# MB_Relay_active_high.net
KiCad netlist of a schematic drawn in EAGLE
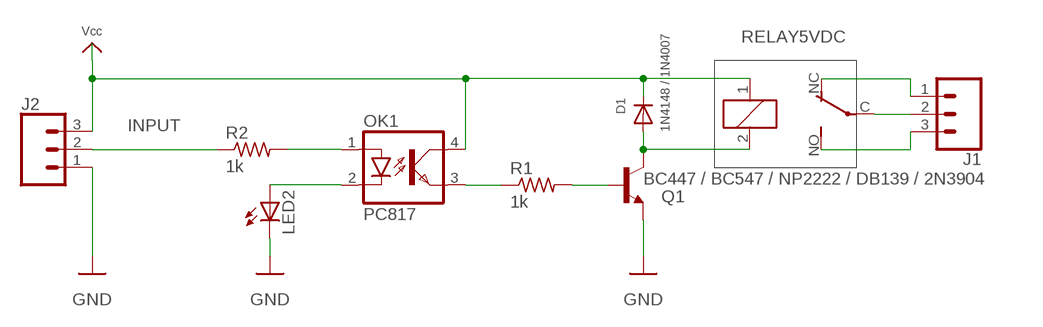
[diagram p0: schematic, sheet 1]

(export (version "E")
  (design (tool "Eeschema 10.0.6"))
  (components
    (comp (ref "D1")
      (value "1N4148 / 1N4007")
      (footprint "eagle-import:DO-1N4148")
      (libsource (lib "eagle-import") (part "DIODEDO-1N4148"))
    )
    (comp (ref "J1")
      (value "CONN_03")
      (footprint "eagle-import:1X03")
      (libsource (lib "eagle-import") (part "CONN_03"))
    )
    (comp (ref "J2")
      (value "CONN_03")
      (footprint "eagle-import:1X03")
      (libsource (lib "eagle-import") (part "CONN_03"))
    )
    (comp (ref "LED2")
      (value "LED3MM")
      (footprint "eagle-import:LED3MM")
      (libsource (lib "eagle-import") (part "LED3MM"))
    )
    (comp (ref "OK1")
      (value "PC817")
      (footprint "eagle-import:DIL04")
      (fields (field (name "MPN") "PC817X4J000F"))
      (libsource (lib "eagle-import") (part "PC817"))
    )
    (comp (ref "Q1")
      (value "BC447 / BC547 / NP2222 / DB139 / 2N3904")
      (footprint "eagle-import:TO92-EBC")
      (libsource (lib "eagle-import") (part "BC447"))
    )
    (comp (ref "R1")
      (value "1k")
      (footprint "eagle-import:0204_7")
      (libsource (lib "eagle-import") (part "R-US_0204/7"))
    )
    (comp (ref "R2")
      (value "1k")
      (footprint "eagle-import:0204_7")
      (libsource (lib "eagle-import") (part "R-US_0204/7"))
    )
    (comp (ref "RELAY5VDC")
      (value "RELAY 5VDC")
      (footprint "eagle-import:CQ1")
      (libsource (lib "eagle-import") (part "CQ1-12V"))
    )
  )
  (nets
    (net (code "1") (name "/INPUT") (class "Default")
      (node (ref "J2") (pin "2") (pinfunction "2_2") (pintype "passive"))
      (node (ref "R2") (pin "1") (pinfunction "1_1") (pintype "passive"))
    )
    (net (code "2") (name "GND") (class "Default")
      (node (ref "J2") (pin "1") (pinfunction "1_1") (pintype "passive"))
      (node (ref "LED2") (pin "K") (pinfunction "C_K") (pintype "passive"))
      (node (ref "Q1") (pin "E") (pinfunction "E_E") (pintype "passive"))
    )
    (net (code "3") (name "Net-(D1-PadA)") (class "Default")
      (node (ref "D1") (pin "A") (pinfunction "A_A") (pintype "passive"))
      (node (ref "Q1") (pin "C") (pinfunction "C_C") (pintype "passive"))
      (node (ref "RELAY5VDC") (pin "2") (pinfunction "2_2") (pintype "passive"))
    )
    (net (code "4") (name "Net-(OK1-A)") (class "Default")
      (node (ref "OK1") (pin "1") (pinfunction "A_1") (pintype "passive"))
      (node (ref "R2") (pin "2") (pinfunction "2_2") (pintype "passive"))
    )
    (net (code "5") (name "Net-(OK1-C)") (class "Default")
      (node (ref "LED2") (pin "A") (pinfunction "A_A") (pintype "passive"))
      (node (ref "OK1") (pin "2") (pinfunction "C_2") (pintype "passive"))
    )
    (net (code "6") (name "Net-(OK1-EMIT)") (class "Default")
      (node (ref "OK1") (pin "3") (pinfunction "EMIT_3") (pintype "passive"))
      (node (ref "R1") (pin "1") (pinfunction "1_1") (pintype "passive"))
    )
    (net (code "7") (name "Net-(Q1-PadB)") (class "Default")
      (node (ref "Q1") (pin "B") (pinfunction "B_B") (pintype "passive"))
      (node (ref "R1") (pin "2") (pinfunction "2_2") (pintype "passive"))
    )
    (net (code "8") (name "Net-(RELAY5VDCB-O)") (class "Default")
      (node (ref "J1") (pin "1") (pinfunction "1_1") (pintype "passive"))
      (node (ref "RELAY5VDC") (pin "NC") (pinfunction "O_NC") (pintype "passive"))
    )
    (net (code "9") (name "Net-(RELAY5VDCB-P)") (class "Default")
      (node (ref "J1") (pin "2") (pinfunction "2_2") (pintype "passive"))
      (node (ref "RELAY5VDC") (pin "C") (pinfunction "P_C") (pintype "passive"))
    )
    (net (code "10") (name "Net-(RELAY5VDCB-S)") (class "Default")
      (node (ref "J1") (pin "3") (pinfunction "3_3") (pintype "passive"))
      (node (ref "RELAY5VDC") (pin "NO") (pinfunction "S_NO") (pintype "passive"))
    )
    (net (code "11") (name "Vcc") (class "Default")
      (node (ref "D1") (pin "C") (pinfunction "C_C") (pintype "passive"))
      (node (ref "J2") (pin "3") (pinfunction "3_3") (pintype "passive"))
      (node (ref "OK1") (pin "4") (pinfunction "COL_4") (pintype "passive"))
      (node (ref "RELAY5VDC") (pin "1") (pinfunction "1_1") (pintype "passive"))
    )
  )
)
